# BOOT_JTAG_AUX.net
KiCad netlist of a schematic drawn in Altium Designer
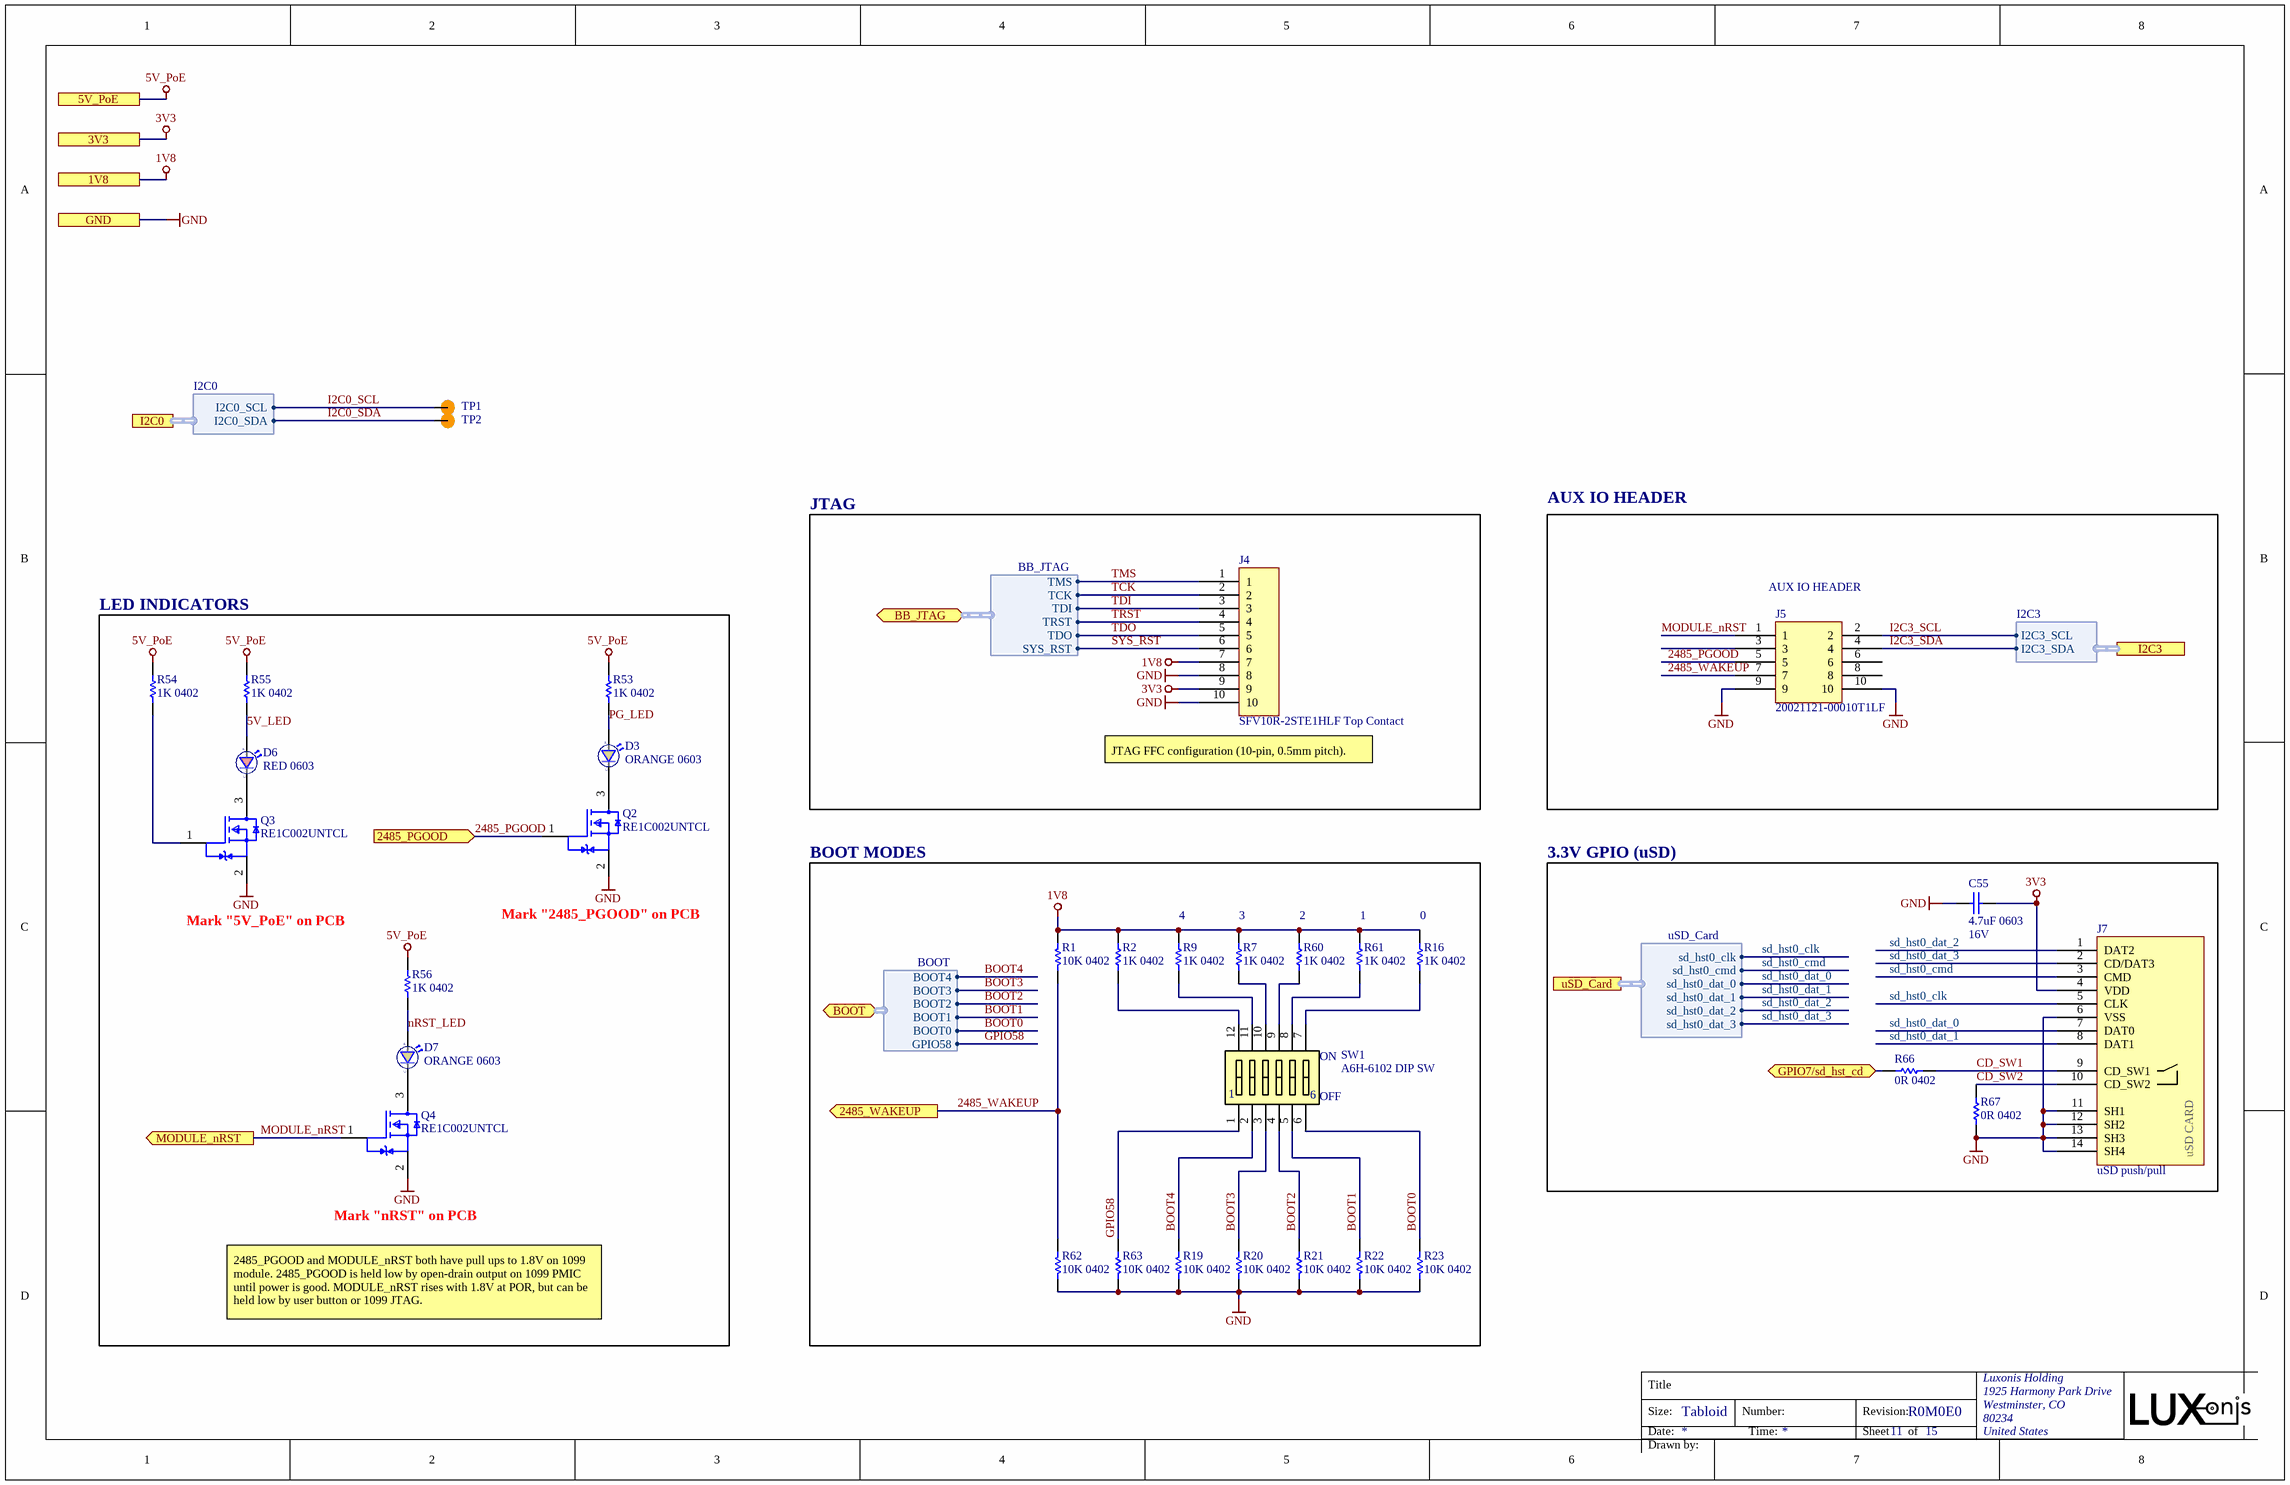
[diagram p0: BOOT_JTAG_AUX.SchDoc]

(export (version "E")
  (design (tool "Eeschema 10.0.6"))
  (components
    (comp (ref "C55")
      (value "4.7uF 0603")
      (footprint "CAPC0603(1608)100_N")
      (description "CAP CER 4.7UF 16V X5R 0603 10%")
      (fields (field (name "TOLERANCE") "10%") (field (name "VOLTAGE RATING") "16V"))
      (libsource (lib "LuxonisMaster") (part "GRM188R61C475KAAJD"))
    )
    (comp (ref "D3")
      (value "ORANGE 0603")
      (footprint "LuxonisMaster:SML_D1xx8W")
      (description "LED ORANGE DIFFUSED 0603 SMD Orange 605nm LED Indication - Discrete 2.2V 0603 (1608 Metric)")
      (libsource (lib "LuxonisMaster") (part "SML-D12D8WT86"))
    )
    (comp (ref "D6")
      (value "RED 0603")
      (footprint "LuxonisMaster:SML_D1xx8W")
      (description "LED RED DIFFUSED 0603 SMD Red 620nm LED Indication - Discrete 2.2V 0603 (1608 Metric)")
      (libsource (lib "LuxonisMaster") (part "SML-D12U8WT86"))
    )
    (comp (ref "D7")
      (value "ORANGE 0603")
      (footprint "LuxonisMaster:SML_D1xx8W")
      (description "LED ORANGE DIFFUSED 0603 SMD Orange 605nm LED Indication - Discrete 2.2V 0603 (1608 Metric)")
      (libsource (lib "LuxonisMaster") (part "SML-D12D8WT86"))
    )
    (comp (ref "J4")
      (value "SFV10R-2STE1HLF Top Contact")
      (footprint "LuxonisMaster:SFV10R-2STE1HLF")
      (description "CONN FFC TOP 10POS 0.50MM R/A")
      (libsource (lib "LuxonisMaster") (part "SFV10R-2STE1HLF"))
    )
    (comp (ref "J5")
      (value "20021121-00010T1LF")
      (footprint "LuxonisMaster:20021121-00010T1LF")
      (description "CONN HEADER SMD 10POS 1.27MM")
      (libsource (lib "LuxonisMaster") (part "20021121-00010T1LF"))
    )
    (comp (ref "J7")
      (value "uSD push/pull")
      (footprint "LuxonisMaster:104031-0811")
      (description "CONN MICRO SD CARD PUSH-PULL R/A")
      (libsource (lib "LuxonisMaster") (part "104031-0811"))
    )
    (comp (ref "Q2")
      (value "RE1C002UNTCL")
      (footprint "LuxonisMaster:RE1C002UNTCL")
      (description "MOSFET N-CH 20V 0.2A EMT3")
      (libsource (lib "LuxonisMaster") (part "RE1C002UNTCL"))
    )
    (comp (ref "Q3")
      (value "RE1C002UNTCL")
      (footprint "LuxonisMaster:RE1C002UNTCL")
      (description "MOSFET N-CH 20V 0.2A EMT3")
      (libsource (lib "LuxonisMaster") (part "RE1C002UNTCL"))
    )
    (comp (ref "Q4")
      (value "RE1C002UNTCL")
      (footprint "LuxonisMaster:RE1C002UNTCL")
      (description "MOSFET N-CH 20V 0.2A EMT3")
      (libsource (lib "LuxonisMaster") (part "RE1C002UNTCL"))
    )
    (comp (ref "R1")
      (value "10K 0402")
      (footprint "RESC0402(1005)_N")
      (fields (field (name "TOLERANCE") "1%"))
      (libsource (lib "LuxonisMaster") (part "RC0402FR-1310KL"))
    )
    (comp (ref "R2")
      (value "1K 0402")
      (footprint "RESC0402(1005)_N")
      (fields (field (name "TOLERANCE") "1%"))
      (libsource (lib "LuxonisMaster") (part "RC0402FR-071KL"))
    )
    (comp (ref "R7")
      (value "1K 0402")
      (footprint "RESC0402(1005)_N")
      (fields (field (name "TOLERANCE") "1%"))
      (libsource (lib "LuxonisMaster") (part "RC0402FR-071KL"))
    )
    (comp (ref "R9")
      (value "1K 0402")
      (footprint "RESC0402(1005)_N")
      (fields (field (name "TOLERANCE") "1%"))
      (libsource (lib "LuxonisMaster") (part "RC0402FR-071KL"))
    )
    (comp (ref "R16")
      (value "1K 0402")
      (footprint "RESC0402(1005)_N")
      (fields (field (name "TOLERANCE") "1%"))
      (libsource (lib "LuxonisMaster") (part "RC0402FR-071KL"))
    )
    (comp (ref "R19")
      (value "10K 0402")
      (footprint "RESC0402(1005)_N")
      (fields (field (name "TOLERANCE") "1%"))
      (libsource (lib "LuxonisMaster") (part "RC0402FR-1310KL"))
    )
    (comp (ref "R20")
      (value "10K 0402")
      (footprint "RESC0402(1005)_N")
      (fields (field (name "TOLERANCE") "1%"))
      (libsource (lib "LuxonisMaster") (part "RC0402FR-1310KL"))
    )
    (comp (ref "R21")
      (value "10K 0402")
      (footprint "RESC0402(1005)_N")
      (fields (field (name "TOLERANCE") "1%"))
      (libsource (lib "LuxonisMaster") (part "RC0402FR-1310KL"))
    )
    (comp (ref "R22")
      (value "10K 0402")
      (footprint "RESC0402(1005)_N")
      (fields (field (name "TOLERANCE") "1%"))
      (libsource (lib "LuxonisMaster") (part "RC0402FR-1310KL"))
    )
    (comp (ref "R23")
      (value "10K 0402")
      (footprint "RESC0402(1005)_N")
      (fields (field (name "TOLERANCE") "1%"))
      (libsource (lib "LuxonisMaster") (part "RC0402FR-1310KL"))
    )
    (comp (ref "R53")
      (value "1K 0402")
      (footprint "RESC0402(1005)_N")
      (fields (field (name "TOLERANCE") "1%"))
      (libsource (lib "LuxonisMaster") (part "RC0402FR-071KL"))
    )
    (comp (ref "R54")
      (value "1K 0402")
      (footprint "RESC0402(1005)_N")
      (fields (field (name "TOLERANCE") "1%"))
      (libsource (lib "LuxonisMaster") (part "RC0402FR-071KL"))
    )
    (comp (ref "R55")
      (value "1K 0402")
      (footprint "RESC0402(1005)_N")
      (fields (field (name "TOLERANCE") "1%"))
      (libsource (lib "LuxonisMaster") (part "RC0402FR-071KL"))
    )
    (comp (ref "R56")
      (value "1K 0402")
      (footprint "RESC0402(1005)_N")
      (fields (field (name "TOLERANCE") "1%"))
      (libsource (lib "LuxonisMaster") (part "RC0402FR-071KL"))
    )
    (comp (ref "R60")
      (value "1K 0402")
      (footprint "RESC0402(1005)_N")
      (fields (field (name "TOLERANCE") "1%"))
      (libsource (lib "LuxonisMaster") (part "RC0402FR-071KL"))
    )
    (comp (ref "R61")
      (value "1K 0402")
      (footprint "RESC0402(1005)_N")
      (fields (field (name "TOLERANCE") "1%"))
      (libsource (lib "LuxonisMaster") (part "RC0402FR-071KL"))
    )
    (comp (ref "R62")
      (value "10K 0402")
      (footprint "RESC0402(1005)_N")
      (fields (field (name "TOLERANCE") "1%"))
      (libsource (lib "LuxonisMaster") (part "RC0402FR-1310KL"))
    )
    (comp (ref "R63")
      (value "10K 0402")
      (footprint "RESC0402(1005)_N")
      (fields (field (name "TOLERANCE") "1%"))
      (libsource (lib "LuxonisMaster") (part "RC0402FR-1310KL"))
    )
    (comp (ref "R66")
      (value "0R 0402")
      (footprint "RESC0402(1005)_N")
      (description "RES SMD 0 OHM JUMPER 1/16W 0402")
      (fields (field (name "TOLERANCE") "5%"))
      (libsource (lib "LuxonisMaster") (part "CRCW04020000Z0ED"))
    )
    (comp (ref "R67")
      (value "0R 0402")
      (footprint "RESC0402(1005)_N")
      (description "RES SMD 0 OHM JUMPER 1/16W 0402")
      (fields (field (name "TOLERANCE") "5%"))
      (libsource (lib "LuxonisMaster") (part "CRCW04020000Z0ED"))
    )
    (comp (ref "SW1")
      (value "A6H-6102 DIP SW")
      (footprint "LuxonisMaster:A6H-610x")
      (description "SWITCH SLIDE DIP SPST 25MA 24V (SEALED)")
      (libsource (lib "LuxonisMaster") (part "A6H-6102"))
    )
    (comp (ref "TP1")
      (value "TP100_200_NS")
      (footprint "TP100_200_NS")
      (libsource (lib "LuxonisMaster") (part "TEST_POINT"))
    )
    (comp (ref "TP2")
      (value "TP100_200_NS")
      (footprint "TP100_200_NS")
      (libsource (lib "LuxonisMaster") (part "TEST_POINT"))
    )
  )
  (nets
    (net (code "6") (name "/5V_LED") (class "Default")
      (node (ref "D6") (pin "2") (pinfunction "A_2") (pintype "passive"))
      (node (ref "R55") (pin "1") (pinfunction "1_1") (pintype "passive"))
    )
    (net (code "7") (name "/2485_PGOOD") (class "Default")
      (node (ref "J5") (pin "5") (pinfunction "5_5") (pintype "passive"))
      (node (ref "Q2") (pin "1") (pinfunction "Gate_1") (pintype "passive"))
    )
    (net (code "8") (name "/2485_WAKEUP") (class "Default")
      (node (ref "J5") (pin "7") (pinfunction "7_7") (pintype "passive"))
      (node (ref "R1") (pin "2") (pinfunction "2_2") (pintype "passive"))
      (node (ref "R62") (pin "1") (pinfunction "1_1") (pintype "passive"))
    )
    (net (code "9") (name "/BOOT0") (class "Default")
      (node (ref "R23") (pin "1") (pinfunction "1_1") (pintype "passive"))
      (node (ref "SW1") (pin "6") (pinfunction "6_6") (pintype "passive"))
    )
    (net (code "10") (name "/BOOT1") (class "Default")
      (node (ref "R22") (pin "1") (pinfunction "1_1") (pintype "passive"))
      (node (ref "SW1") (pin "5") (pinfunction "5_5") (pintype "passive"))
    )
    (net (code "11") (name "/BOOT2") (class "Default")
      (node (ref "R21") (pin "1") (pinfunction "1_1") (pintype "passive"))
      (node (ref "SW1") (pin "4") (pinfunction "4_4") (pintype "passive"))
    )
    (net (code "12") (name "/BOOT3") (class "Default")
      (node (ref "R20") (pin "1") (pinfunction "1_1") (pintype "passive"))
      (node (ref "SW1") (pin "3") (pinfunction "3_3") (pintype "passive"))
    )
    (net (code "13") (name "/BOOT4") (class "Default")
      (node (ref "R19") (pin "1") (pinfunction "1_1") (pintype "passive"))
      (node (ref "SW1") (pin "2") (pinfunction "2_2") (pintype "passive"))
    )
    (net (code "14") (name "/CD_SW1") (class "Default")
      (node (ref "J7") (pin "9") (pinfunction "CD_SW1_9") (pintype "passive"))
      (node (ref "R66") (pin "1") (pinfunction "1_1") (pintype "passive"))
    )
    (net (code "15") (name "/CD_SW2") (class "Default")
      (node (ref "J7") (pin "10") (pinfunction "CD_SW2_10") (pintype "passive"))
      (node (ref "R67") (pin "2") (pinfunction "2_2") (pintype "passive"))
    )
    (net (code "16") (name "/GPIO7{slash}sd_hst_cd") (class "Default")
      (node (ref "R66") (pin "2") (pinfunction "2_2") (pintype "passive"))
    )
    (net (code "17") (name "/GPIO58") (class "Default")
      (node (ref "R63") (pin "1") (pinfunction "1_1") (pintype "passive"))
      (node (ref "SW1") (pin "1") (pinfunction "1_1") (pintype "passive"))
    )
    (net (code "18") (name "/I2C0_SCL") (class "Default") (node (ref "TP1") (pin "1") (pintype "passive")))
    (net (code "19") (name "/I2C0_SDA") (class "Default") (node (ref "TP2") (pin "1") (pintype "passive")))
    (net (code "20") (name "/I2C3_SCL") (class "Default")
      (node (ref "J5") (pin "2") (pinfunction "2_2") (pintype "passive"))
    )
    (net (code "21") (name "/I2C3_SDA") (class "Default")
      (node (ref "J5") (pin "4") (pinfunction "4_4") (pintype "passive"))
    )
    (net (code "22") (name "/MODULE_nRST") (class "Default")
      (node (ref "J5") (pin "1") (pinfunction "1_1") (pintype "passive"))
      (node (ref "Q4") (pin "1") (pinfunction "Gate_1") (pintype "passive"))
    )
    (net (code "23") (name "/PG_LED") (class "Default")
      (node (ref "D3") (pin "2") (pinfunction "A_2") (pintype "passive"))
      (node (ref "R53") (pin "1") (pinfunction "1_1") (pintype "passive"))
    )
    (net (code "24") (name "/SYS_RST") (class "Default")
      (node (ref "J4") (pin "6") (pinfunction "6_6") (pintype "passive"))
    )
    (net (code "25") (name "/TCK") (class "Default")
      (node (ref "J4") (pin "2") (pinfunction "2_2") (pintype "passive"))
    )
    (net (code "26") (name "/TDI") (class "Default")
      (node (ref "J4") (pin "3") (pinfunction "3_3") (pintype "passive"))
    )
    (net (code "27") (name "/TDO") (class "Default")
      (node (ref "J4") (pin "5") (pinfunction "5_5") (pintype "passive"))
    )
    (net (code "28") (name "/TMS") (class "Default")
      (node (ref "J4") (pin "1") (pinfunction "1_1") (pintype "passive"))
    )
    (net (code "29") (name "/TRST") (class "Default")
      (node (ref "J4") (pin "4") (pinfunction "4_4") (pintype "passive"))
    )
    (net (code "30") (name "/nRST_LED") (class "Default")
      (node (ref "D7") (pin "2") (pinfunction "A_2") (pintype "passive"))
      (node (ref "R56") (pin "1") (pinfunction "1_1") (pintype "passive"))
    )
    (net (code "31") (name "/sd_hst0_clk") (class "Default")
      (node (ref "J7") (pin "5") (pinfunction "CLK_5") (pintype "passive"))
    )
    (net (code "32") (name "/sd_hst0_cmd") (class "Default")
      (node (ref "J7") (pin "3") (pinfunction "CMD_3") (pintype "passive"))
    )
    (net (code "33") (name "/sd_hst0_dat_0") (class "Default")
      (node (ref "J7") (pin "7") (pinfunction "DAT0_7") (pintype "passive"))
    )
    (net (code "34") (name "/sd_hst0_dat_1") (class "Default")
      (node (ref "J7") (pin "8") (pinfunction "DAT1_8") (pintype "passive"))
    )
    (net (code "35") (name "/sd_hst0_dat_2") (class "Default")
      (node (ref "J7") (pin "1") (pinfunction "DAT2_1") (pintype "passive"))
    )
    (net (code "36") (name "/sd_hst0_dat_3") (class "Default")
      (node (ref "J7") (pin "2") (pinfunction "CD/DAT3_2") (pintype "passive"))
    )
    (net (code "42") (name "1V8") (class "Default")
      (node (ref "J4") (pin "7") (pinfunction "7_7") (pintype "passive"))
      (node (ref "R1") (pin "1") (pinfunction "1_1") (pintype "passive"))
      (node (ref "R16") (pin "2") (pinfunction "2_2") (pintype "passive"))
      (node (ref "R2") (pin "2") (pinfunction "2_2") (pintype "passive"))
      (node (ref "R60") (pin "2") (pinfunction "2_2") (pintype "passive"))
      (node (ref "R61") (pin "2") (pinfunction "2_2") (pintype "passive"))
      (node (ref "R7") (pin "2") (pinfunction "2_2") (pintype "passive"))
      (node (ref "R9") (pin "2") (pinfunction "2_2") (pintype "passive"))
    )
    (net (code "43") (name "3V3") (class "Default")
      (node (ref "C55") (pin "2") (pinfunction "2_2") (pintype "passive"))
      (node (ref "J4") (pin "9") (pinfunction "9_9") (pintype "passive"))
      (node (ref "J7") (pin "4") (pinfunction "VDD_4") (pintype "passive"))
    )
    (net (code "44") (name "5V_PoE") (class "Default")
      (node (ref "R53") (pin "2") (pinfunction "2_2") (pintype "passive"))
      (node (ref "R54") (pin "2") (pinfunction "2_2") (pintype "passive"))
      (node (ref "R55") (pin "2") (pinfunction "2_2") (pintype "passive"))
      (node (ref "R56") (pin "2") (pinfunction "2_2") (pintype "passive"))
    )
    (net (code "45") (name "GND") (class "Default")
      (node (ref "C55") (pin "1") (pinfunction "1_1") (pintype "passive"))
      (node (ref "J4") (pin "10") (pinfunction "10_10") (pintype "passive"))
      (node (ref "J4") (pin "8") (pinfunction "8_8") (pintype "passive"))
      (node (ref "J5") (pin "10") (pinfunction "10_10") (pintype "passive"))
      (node (ref "J5") (pin "9") (pinfunction "9_9") (pintype "passive"))
      (node (ref "J7") (pin "11") (pinfunction "SH1_11") (pintype "passive"))
      (node (ref "J7") (pin "12") (pinfunction "SH2_12") (pintype "passive"))
      (node (ref "J7") (pin "13") (pinfunction "SH3_13") (pintype "passive"))
      (node (ref "J7") (pin "14") (pinfunction "SH4_14") (pintype "passive"))
      (node (ref "J7") (pin "6") (pinfunction "VSS_6") (pintype "passive"))
      (node (ref "Q2") (pin "2") (pinfunction "Source_2") (pintype "passive"))
      (node (ref "Q3") (pin "2") (pinfunction "Source_2") (pintype "passive"))
      (node (ref "Q4") (pin "2") (pinfunction "Source_2") (pintype "passive"))
      (node (ref "R19") (pin "2") (pinfunction "2_2") (pintype "passive"))
      (node (ref "R20") (pin "2") (pinfunction "2_2") (pintype "passive"))
      (node (ref "R21") (pin "2") (pinfunction "2_2") (pintype "passive"))
      (node (ref "R22") (pin "2") (pinfunction "2_2") (pintype "passive"))
      (node (ref "R23") (pin "2") (pinfunction "2_2") (pintype "passive"))
      (node (ref "R62") (pin "2") (pinfunction "2_2") (pintype "passive"))
      (node (ref "R63") (pin "2") (pinfunction "2_2") (pintype "passive"))
      (node (ref "R67") (pin "1") (pinfunction "1_1") (pintype "passive"))
    )
    (net (code "46") (name "Net-(D3-C)") (class "Default")
      (node (ref "D3") (pin "1") (pinfunction "C_1") (pintype "passive"))
      (node (ref "Q2") (pin "3") (pinfunction "Drain_3") (pintype "passive"))
    )
    (net (code "47") (name "Net-(D6-C)") (class "Default")
      (node (ref "D6") (pin "1") (pinfunction "C_1") (pintype "passive"))
      (node (ref "Q3") (pin "3") (pinfunction "Drain_3") (pintype "passive"))
    )
    (net (code "48") (name "Net-(D7-C)") (class "Default")
      (node (ref "D7") (pin "1") (pinfunction "C_1") (pintype "passive"))
      (node (ref "Q4") (pin "3") (pinfunction "Drain_3") (pintype "passive"))
    )
    (net (code "49") (name "Net-(Q3-Gate)") (class "Default")
      (node (ref "Q3") (pin "1") (pinfunction "Gate_1") (pintype "passive"))
      (node (ref "R54") (pin "1") (pinfunction "1_1") (pintype "passive"))
    )
    (net (code "50") (name "Net-(R2-Pad1)") (class "Default")
      (node (ref "R2") (pin "1") (pinfunction "1_1") (pintype "passive"))
      (node (ref "SW1") (pin "12") (pinfunction "12_12") (pintype "passive"))
    )
    (net (code "51") (name "Net-(R7-Pad1)") (class "Default")
      (node (ref "R7") (pin "1") (pinfunction "1_1") (pintype "passive"))
      (node (ref "SW1") (pin "10") (pinfunction "10_10") (pintype "passive"))
    )
    (net (code "52") (name "Net-(R9-Pad1)") (class "Default")
      (node (ref "R9") (pin "1") (pinfunction "1_1") (pintype "passive"))
      (node (ref "SW1") (pin "11") (pinfunction "11_11") (pintype "passive"))
    )
    (net (code "53") (name "Net-(R16-Pad1)") (class "Default")
      (node (ref "R16") (pin "1") (pinfunction "1_1") (pintype "passive"))
      (node (ref "SW1") (pin "7") (pinfunction "7_7") (pintype "passive"))
    )
    (net (code "54") (name "Net-(R60-Pad1)") (class "Default")
      (node (ref "R60") (pin "1") (pinfunction "1_1") (pintype "passive"))
      (node (ref "SW1") (pin "9") (pinfunction "9_9") (pintype "passive"))
    )
    (net (code "55") (name "Net-(R61-Pad1)") (class "Default")
      (node (ref "R61") (pin "1") (pinfunction "1_1") (pintype "passive"))
      (node (ref "SW1") (pin "8") (pinfunction "8_8") (pintype "passive"))
    )
    (net (code "56") (name "unconnected-(J5-Pad3)") (class "Default")
      (node (ref "J5") (pin "3") (pinfunction "3_3") (pintype "passive"))
    )
    (net (code "57") (name "unconnected-(J5-Pad6)") (class "Default")
      (node (ref "J5") (pin "6") (pinfunction "6_6") (pintype "passive"))
    )
    (net (code "58") (name "unconnected-(J5-Pad8)") (class "Default")
      (node (ref "J5") (pin "8") (pinfunction "8_8") (pintype "passive"))
    )
  )
)
